# untitled.net
KiCad netlist of a schematic drawn in EAGLE
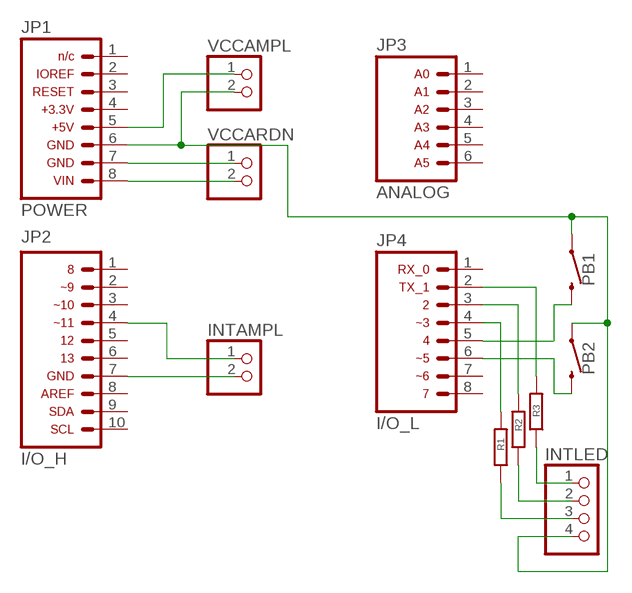
[diagram p0: schematic, sheet 1]

(export (version "E")
  (design (tool "Eeschema 10.0.6"))
  (components
    (comp (ref "INTAMPL")
      (value "PINHD-1X2")
      (footprint "eagle-import:1X02")
      (libsource (lib "eagle-import") (part "PINHD-1X2"))
    )
    (comp (ref "INTLED")
      (value "PINHD-1X4")
      (footprint "eagle-import:1X04")
      (libsource (lib "eagle-import") (part "PINHD-1X4"))
    )
    (comp (ref "JP1")
      (value "ARDUINO_CONN-POWERSIP")
      (footprint "eagle-import:CONN-1X08")
      (libsource (lib "eagle-import") (part "ARDUINO_CONN-POWERSIP"))
    )
    (comp (ref "JP2")
      (value "ARDUINO_CONN-IO_HSIP")
      (footprint "eagle-import:CONN-1X10")
      (libsource (lib "eagle-import") (part "ARDUINO_CONN-IO_HSIP"))
    )
    (comp (ref "JP3")
      (value "ARDUINO_CONN-ANALOGSIP")
      (footprint "eagle-import:CONN-1X06")
      (libsource (lib "eagle-import") (part "ARDUINO_CONN-ANALOGSIP"))
    )
    (comp (ref "JP4")
      (value "ARDUINO_CONN-IO_LSIP")
      (footprint "eagle-import:CONN-1X08")
      (libsource (lib "eagle-import") (part "ARDUINO_CONN-IO_LSIP"))
    )
    (comp (ref "PB1")
      (value "MOMENTARY-SWITCH-SPST-PTH-6.0MM")
      (footprint "eagle-import:TACTILE_SWITCH_PTH_6.0MM")
      (libsource (lib "eagle-import") (part "MOMENTARY-SWITCH-SPST-PTH-6.0MM"))
    )
    (comp (ref "PB2")
      (value "MOMENTARY-SWITCH-SPST-PTH-6.0MM")
      (footprint "eagle-import:TACTILE_SWITCH_PTH_6.0MM")
      (libsource (lib "eagle-import") (part "MOMENTARY-SWITCH-SPST-PTH-6.0MM"))
    )
    (comp (ref "R1")
      (value "R-EU_0204/7")
      (footprint "eagle-import:0204_7")
      (libsource (lib "eagle-import") (part "R-EU_0204/7"))
    )
    (comp (ref "R2")
      (value "R-EU_0204/7")
      (footprint "eagle-import:0204_7")
      (libsource (lib "eagle-import") (part "R-EU_0204/7"))
    )
    (comp (ref "R3")
      (value "R-EU_0204/7")
      (footprint "eagle-import:0204_7")
      (libsource (lib "eagle-import") (part "R-EU_0204/7"))
    )
    (comp (ref "VCCAMPL")
      (value "PINHD-1X2")
      (footprint "eagle-import:1X02")
      (libsource (lib "eagle-import") (part "PINHD-1X2"))
    )
    (comp (ref "VCCARDN")
      (value "PINHD-1X2")
      (footprint "eagle-import:1X02")
      (libsource (lib "eagle-import") (part "PINHD-1X2"))
    )
  )
  (nets
    (net (code "1") (name "Net-(INTAMPL-Pad1)") (class "Default")
      (node (ref "INTAMPL") (pin "1") (pinfunction "1_1") (pintype "passive"))
      (node (ref "JP2") (pin "4") (pinfunction "4_4") (pintype "passive"))
    )
    (net (code "2") (name "Net-(INTAMPL-Pad2)") (class "Default")
      (node (ref "INTAMPL") (pin "2") (pinfunction "2_2") (pintype "passive"))
      (node (ref "JP2") (pin "7") (pinfunction "7_7") (pintype "passive"))
    )
    (net (code "3") (name "Net-(INTLED-Pad1)") (class "Default")
      (node (ref "INTLED") (pin "1") (pinfunction "1_1") (pintype "passive"))
      (node (ref "R3") (pin "1") (pinfunction "1_1") (pintype "passive"))
    )
    (net (code "4") (name "Net-(INTLED-Pad2)") (class "Default")
      (node (ref "INTLED") (pin "2") (pinfunction "2_2") (pintype "passive"))
      (node (ref "R2") (pin "1") (pinfunction "1_1") (pintype "passive"))
    )
    (net (code "5") (name "Net-(INTLED-Pad3)") (class "Default")
      (node (ref "INTLED") (pin "3") (pinfunction "3_3") (pintype "passive"))
      (node (ref "R1") (pin "1") (pinfunction "1_1") (pintype "passive"))
    )
    (net (code "6") (name "Net-(INTLED-Pad4)") (class "Default")
      (node (ref "INTLED") (pin "4") (pinfunction "4_4") (pintype "passive"))
      (node (ref "JP1") (pin "6") (pinfunction "6_6") (pintype "passive"))
      (node (ref "PB1") (pin "1") (pinfunction "1_1") (pintype "passive"))
      (node (ref "PB2") (pin "1") (pinfunction "1_1") (pintype "passive"))
      (node (ref "VCCAMPL") (pin "2") (pinfunction "2_2") (pintype "passive"))
    )
    (net (code "7") (name "Net-(JP1-Pad5)") (class "Default")
      (node (ref "JP1") (pin "5") (pinfunction "5_5") (pintype "passive"))
      (node (ref "VCCAMPL") (pin "1") (pinfunction "1_1") (pintype "passive"))
    )
    (net (code "8") (name "Net-(JP1-Pad7)") (class "Default")
      (node (ref "JP1") (pin "7") (pinfunction "7_7") (pintype "passive"))
      (node (ref "VCCARDN") (pin "1") (pinfunction "1_1") (pintype "passive"))
    )
    (net (code "9") (name "Net-(JP1-Pad8)") (class "Default")
      (node (ref "JP1") (pin "8") (pinfunction "8_8") (pintype "passive"))
      (node (ref "VCCARDN") (pin "2") (pinfunction "2_2") (pintype "passive"))
    )
    (net (code "10") (name "Net-(JP4-Pad2)") (class "Default")
      (node (ref "JP4") (pin "2") (pinfunction "2_2") (pintype "passive"))
      (node (ref "R3") (pin "2") (pinfunction "2_2") (pintype "passive"))
    )
    (net (code "11") (name "Net-(JP4-Pad3)") (class "Default")
      (node (ref "JP4") (pin "3") (pinfunction "3_3") (pintype "passive"))
      (node (ref "R2") (pin "2") (pinfunction "2_2") (pintype "passive"))
    )
    (net (code "12") (name "Net-(JP4-Pad4)") (class "Default")
      (node (ref "JP4") (pin "4") (pinfunction "4_4") (pintype "passive"))
      (node (ref "R1") (pin "2") (pinfunction "2_2") (pintype "passive"))
    )
    (net (code "13") (name "Net-(PB1-2)") (class "Default")
      (node (ref "JP4") (pin "5") (pinfunction "5_5") (pintype "passive"))
      (node (ref "PB1") (pin "3") (pinfunction "2_3") (pintype "passive"))
    )
    (net (code "14") (name "Net-(PB2-2)") (class "Default")
      (node (ref "JP4") (pin "6") (pinfunction "6_6") (pintype "passive"))
      (node (ref "PB2") (pin "3") (pinfunction "2_3") (pintype "passive"))
    )
    (net (code "15") (name "unconnected-(JP1-Pad1)") (class "Default")
      (node (ref "JP1") (pin "1") (pinfunction "1_1") (pintype "passive"))
    )
    (net (code "16") (name "unconnected-(JP1-Pad2)") (class "Default")
      (node (ref "JP1") (pin "2") (pinfunction "2_2") (pintype "passive"))
    )
    (net (code "17") (name "unconnected-(JP1-Pad3)") (class "Default")
      (node (ref "JP1") (pin "3") (pinfunction "3_3") (pintype "passive"))
    )
    (net (code "18") (name "unconnected-(JP1-Pad4)") (class "Default")
      (node (ref "JP1") (pin "4") (pinfunction "4_4") (pintype "passive"))
    )
    (net (code "19") (name "unconnected-(JP2-Pad1)") (class "Default")
      (node (ref "JP2") (pin "1") (pinfunction "1_1") (pintype "passive"))
    )
    (net (code "20") (name "unconnected-(JP2-Pad2)") (class "Default")
      (node (ref "JP2") (pin "2") (pinfunction "2_2") (pintype "passive"))
    )
    (net (code "21") (name "unconnected-(JP2-Pad3)") (class "Default")
      (node (ref "JP2") (pin "3") (pinfunction "3_3") (pintype "passive"))
    )
    (net (code "22") (name "unconnected-(JP2-Pad5)") (class "Default")
      (node (ref "JP2") (pin "5") (pinfunction "5_5") (pintype "passive"))
    )
    (net (code "23") (name "unconnected-(JP2-Pad6)") (class "Default")
      (node (ref "JP2") (pin "6") (pinfunction "6_6") (pintype "passive"))
    )
    (net (code "24") (name "unconnected-(JP2-Pad8)") (class "Default")
      (node (ref "JP2") (pin "8") (pinfunction "8_8") (pintype "passive"))
    )
    (net (code "25") (name "unconnected-(JP2-Pad9)") (class "Default")
      (node (ref "JP2") (pin "9") (pinfunction "9_9") (pintype "passive"))
    )
    (net (code "26") (name "unconnected-(JP2-Pad10)") (class "Default")
      (node (ref "JP2") (pin "10") (pinfunction "10_10") (pintype "passive"))
    )
    (net (code "27") (name "unconnected-(JP3-Pad1)") (class "Default")
      (node (ref "JP3") (pin "1") (pinfunction "1_1") (pintype "passive"))
    )
    (net (code "28") (name "unconnected-(JP3-Pad2)") (class "Default")
      (node (ref "JP3") (pin "2") (pinfunction "2_2") (pintype "passive"))
    )
    (net (code "29") (name "unconnected-(JP3-Pad3)") (class "Default")
      (node (ref "JP3") (pin "3") (pinfunction "3_3") (pintype "passive"))
    )
    (net (code "30") (name "unconnected-(JP3-Pad4)") (class "Default")
      (node (ref "JP3") (pin "4") (pinfunction "4_4") (pintype "passive"))
    )
    (net (code "31") (name "unconnected-(JP3-Pad5)") (class "Default")
      (node (ref "JP3") (pin "5") (pinfunction "5_5") (pintype "passive"))
    )
    (net (code "32") (name "unconnected-(JP3-Pad6)") (class "Default")
      (node (ref "JP3") (pin "6") (pinfunction "6_6") (pintype "passive"))
    )
    (net (code "33") (name "unconnected-(JP4-Pad1)") (class "Default")
      (node (ref "JP4") (pin "1") (pinfunction "1_1") (pintype "passive"))
    )
    (net (code "34") (name "unconnected-(JP4-Pad7)") (class "Default")
      (node (ref "JP4") (pin "7") (pinfunction "7_7") (pintype "passive"))
    )
    (net (code "35") (name "unconnected-(JP4-Pad8)") (class "Default")
      (node (ref "JP4") (pin "8") (pinfunction "8_8") (pintype "passive"))
    )
  )
)
